# cardspoofer.net
KiCad netlist of a schematic drawn in EAGLE
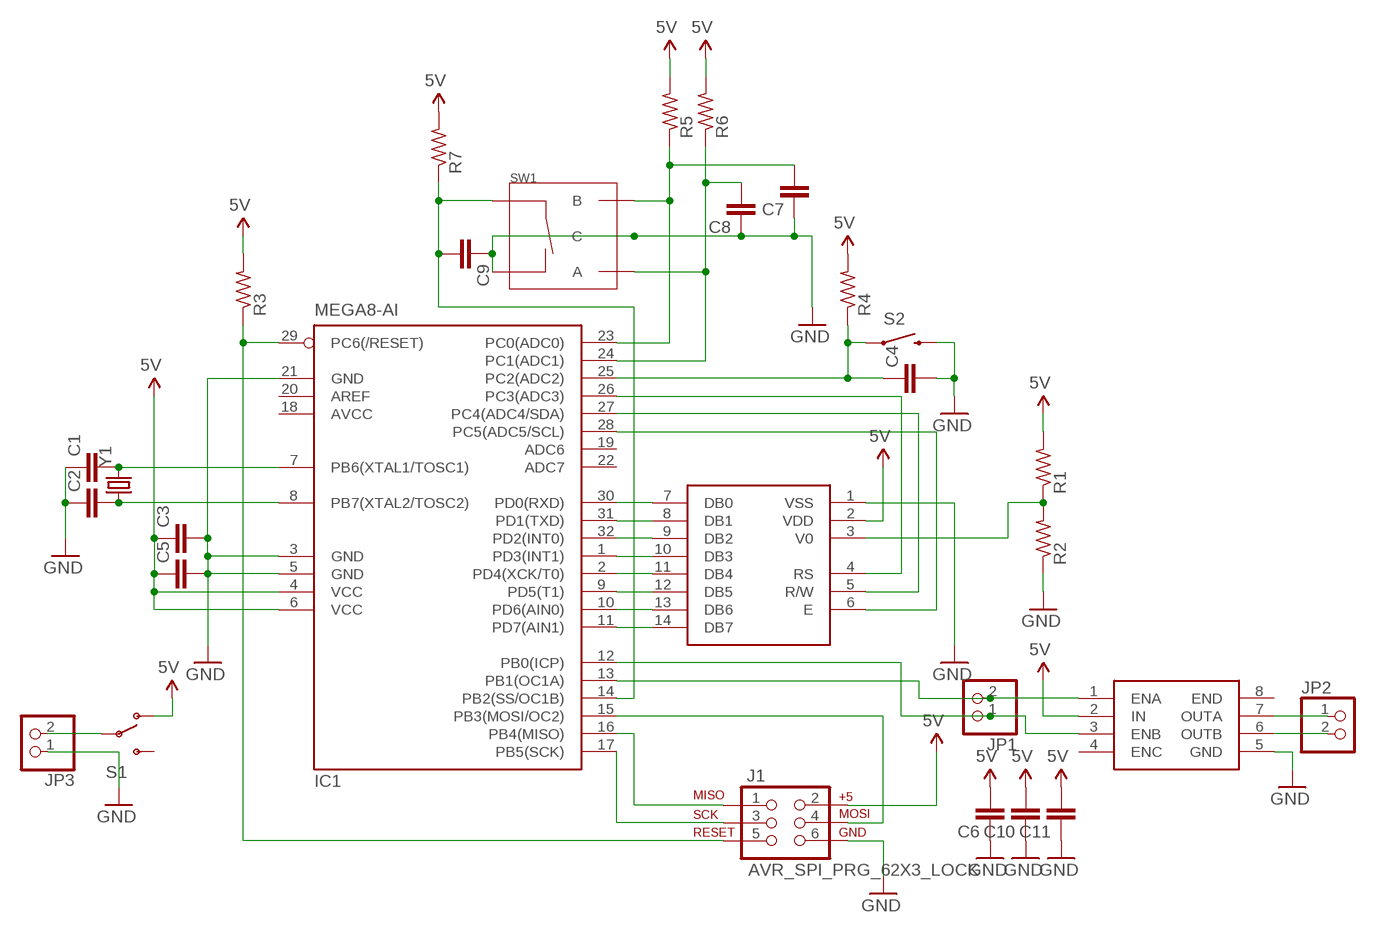
[diagram p0: schematic, sheet 1]

(export (version "E")
  (design (tool "Eeschema 10.0.6"))
  (components
    (comp (ref "C1")
      (value "C-EUC0805K")
      (footprint "eagle-import:C0805K")
      (libsource (lib "eagle-import") (part "C-EUC0805K"))
    )
    (comp (ref "C2")
      (value "C-EUC0805K")
      (footprint "eagle-import:C0805K")
      (libsource (lib "eagle-import") (part "C-EUC0805K"))
    )
    (comp (ref "C3")
      (value "C-EUC0805K")
      (footprint "eagle-import:C0805K")
      (libsource (lib "eagle-import") (part "C-EUC0805K"))
    )
    (comp (ref "C4")
      (value "C-EUC0805K")
      (footprint "eagle-import:C0805K")
      (libsource (lib "eagle-import") (part "C-EUC0805K"))
    )
    (comp (ref "C5")
      (value "C-EUC0805K")
      (footprint "eagle-import:C0805K")
      (libsource (lib "eagle-import") (part "C-EUC0805K"))
    )
    (comp (ref "C6")
      (value "C-EUC0805K")
      (footprint "eagle-import:C0805K")
      (libsource (lib "eagle-import") (part "C-EUC0805K"))
    )
    (comp (ref "C7")
      (value "C-EUC0805K")
      (footprint "eagle-import:C0805K")
      (libsource (lib "eagle-import") (part "C-EUC0805K"))
    )
    (comp (ref "C8")
      (value "C-EUC0805K")
      (footprint "eagle-import:C0805K")
      (libsource (lib "eagle-import") (part "C-EUC0805K"))
    )
    (comp (ref "C9")
      (value "C-EUC0805K")
      (footprint "eagle-import:C0805K")
      (libsource (lib "eagle-import") (part "C-EUC0805K"))
    )
    (comp (ref "C10")
      (value "C-EUC0805K")
      (footprint "eagle-import:C0805K")
      (libsource (lib "eagle-import") (part "C-EUC0805K"))
    )
    (comp (ref "C11")
      (value "C-EUC0805K")
      (footprint "eagle-import:C0805K")
      (libsource (lib "eagle-import") (part "C-EUC0805K"))
    )
    (comp (ref "IC1")
      (value "MEGA8-AI")
      (footprint "eagle-import:TQFP32-08")
      (fields (field (name "MPN") "ATMEGA8-16AU"))
      (libsource (lib "eagle-import") (part "MEGA8-AI"))
    )
    (comp (ref "J1")
      (value "AVR_SPI_PRG_62X3_LOCK")
      (footprint "eagle-import:2X3_LOCK")
      (libsource (lib "eagle-import") (part "AVR_SPI_PRG_62X3_LOCK"))
    )
    (comp (ref "JP1")
      (value "PINHD-1X2")
      (footprint "eagle-import:1X02")
      (libsource (lib "eagle-import") (part "PINHD-1X2"))
    )
    (comp (ref "JP2")
      (value "PINHD-1X2")
      (footprint "eagle-import:1X02")
      (libsource (lib "eagle-import") (part "PINHD-1X2"))
    )
    (comp (ref "JP3")
      (value "PINHD-1X2")
      (footprint "eagle-import:1X02")
      (libsource (lib "eagle-import") (part "PINHD-1X2"))
    )
    (comp (ref "R1")
      (value "R-US_R0805")
      (footprint "eagle-import:R0805")
      (libsource (lib "eagle-import") (part "R-US_R0805"))
    )
    (comp (ref "R2")
      (value "R-US_R0805")
      (footprint "eagle-import:R0805")
      (libsource (lib "eagle-import") (part "R-US_R0805"))
    )
    (comp (ref "R3")
      (value "R-US_R0805")
      (footprint "eagle-import:R0805")
      (libsource (lib "eagle-import") (part "R-US_R0805"))
    )
    (comp (ref "R4")
      (value "R-US_R0805")
      (footprint "eagle-import:R0805")
      (libsource (lib "eagle-import") (part "R-US_R0805"))
    )
    (comp (ref "R5")
      (value "R-US_R0805")
      (footprint "eagle-import:R0805")
      (libsource (lib "eagle-import") (part "R-US_R0805"))
    )
    (comp (ref "R6")
      (value "R-US_R0805")
      (footprint "eagle-import:R0805")
      (libsource (lib "eagle-import") (part "R-US_R0805"))
    )
    (comp (ref "R7")
      (value "R-US_R0805")
      (footprint "eagle-import:R0805")
      (libsource (lib "eagle-import") (part "R-US_R0805"))
    )
    (comp (ref "S1")
      (value "SWITCH-SPDTSMD")
      (footprint "eagle-import:AYZ0202")
      (libsource (lib "eagle-import") (part "SWITCH-SPDTSMD"))
    )
    (comp (ref "S2")
      (value "SWITCH-MOMENTARY-2-SMD-1101NE")
      (footprint "eagle-import:TACTILE-SWITCH-1101NE")
      (libsource (lib "eagle-import") (part "SWITCH-MOMENTARY-2-SMD-1101NE"))
    )
    (comp (ref "SW1")
      (value "ROTARTY_ENCODER")
      (footprint "eagle-import:ROTARY_ENC_PLAIN")
      (libsource (lib "eagle-import") (part "ROTARTY_ENCODER"))
    )
    (comp (ref "U$1")
      (value "LCD")
      (footprint "eagle-import:NHD-0208AZ-RN-YBW-ND")
      (libsource (lib "eagle-import") (part "LCD"))
    )
    (comp (ref "U$2")
      (value "HBRIDGE")
      (footprint "eagle-import:H-BRIDGE")
      (libsource (lib "eagle-import") (part "HBRIDGE"))
    )
    (comp (ref "Y1")
      (value "CRYSTAL5X3")
      (footprint "eagle-import:CRYSTAL-SMD-5X3")
      (libsource (lib "eagle-import") (part "CRYSTAL5X3"))
    )
  )
  (nets
    (net (code "1") (name "/AVCC") (class "Default")
      (node (ref "IC1") (pin "18") (pinfunction "AVCC_18") (pintype "power_in"))
    )
    (net (code "2") (name "5V") (class "Default")
      (node (ref "C10") (pin "2") (pinfunction "2_2") (pintype "passive"))
      (node (ref "C11") (pin "2") (pinfunction "2_2") (pintype "passive"))
      (node (ref "C3") (pin "1") (pinfunction "1_1") (pintype "passive"))
      (node (ref "C5") (pin "1") (pinfunction "1_1") (pintype "passive"))
      (node (ref "C6") (pin "2") (pinfunction "2_2") (pintype "passive"))
      (node (ref "IC1") (pin "4") (pinfunction "VCC_4") (pintype "power_in"))
      (node (ref "IC1") (pin "6") (pinfunction "VCC_6") (pintype "power_in"))
      (node (ref "J1") (pin "2") (pinfunction "2_2") (pintype "passive"))
      (node (ref "R1") (pin "2") (pinfunction "2_2") (pintype "passive"))
      (node (ref "R3") (pin "2") (pinfunction "2_2") (pintype "passive"))
      (node (ref "R4") (pin "2") (pinfunction "2_2") (pintype "passive"))
      (node (ref "R5") (pin "2") (pinfunction "2_2") (pintype "passive"))
      (node (ref "R6") (pin "2") (pinfunction "2_2") (pintype "passive"))
      (node (ref "R7") (pin "2") (pinfunction "2_2") (pintype "passive"))
      (node (ref "S1") (pin "1") (pinfunction "O_1") (pintype "passive"))
      (node (ref "U$1") (pin "2") (pinfunction "VDD_2") (pintype "bidirectional"))
      (node (ref "U$2") (pin "2") (pinfunction "IN_2") (pintype "bidirectional"))
    )
    (net (code "3") (name "GND") (class "Default")
      (node (ref "C1") (pin "1") (pinfunction "1_1") (pintype "passive"))
      (node (ref "C10") (pin "1") (pinfunction "1_1") (pintype "passive"))
      (node (ref "C11") (pin "1") (pinfunction "1_1") (pintype "passive"))
      (node (ref "C2") (pin "1") (pinfunction "1_1") (pintype "passive"))
      (node (ref "C3") (pin "2") (pinfunction "2_2") (pintype "passive"))
      (node (ref "C4") (pin "2") (pinfunction "2_2") (pintype "passive"))
      (node (ref "C5") (pin "2") (pinfunction "2_2") (pintype "passive"))
      (node (ref "C6") (pin "1") (pinfunction "1_1") (pintype "passive"))
      (node (ref "C7") (pin "1") (pinfunction "1_1") (pintype "passive"))
      (node (ref "C8") (pin "1") (pinfunction "1_1") (pintype "passive"))
      (node (ref "C9") (pin "1") (pinfunction "1_1") (pintype "passive"))
      (node (ref "IC1") (pin "21") (pinfunction "GND_21") (pintype "power_in"))
      (node (ref "IC1") (pin "3") (pinfunction "GND_3") (pintype "power_in"))
      (node (ref "IC1") (pin "5") (pinfunction "GND_5") (pintype "power_in"))
      (node (ref "J1") (pin "6") (pinfunction "6_6") (pintype "passive"))
      (node (ref "JP3") (pin "1") (pinfunction "1_1") (pintype "passive"))
      (node (ref "R2") (pin "1") (pinfunction "1_1") (pintype "passive"))
      (node (ref "S2") (pin "2") (pinfunction "2_2") (pintype "passive"))
      (node (ref "SW1") (pin "C") (pinfunction "C_C") (pintype "bidirectional"))
      (node (ref "SW1") (pin "SW-") (pinfunction "SW-_SW-") (pintype "bidirectional"))
      (node (ref "U$1") (pin "1") (pinfunction "VSS_1") (pintype "bidirectional"))
      (node (ref "U$2") (pin "5") (pinfunction "GND_5") (pintype "bidirectional"))
    )
    (net (code "4") (name "Net-(IC1-PB0(ICP))") (class "Default")
      (node (ref "IC1") (pin "12") (pinfunction "PB0(ICP)_12") (pintype "bidirectional"))
      (node (ref "JP1") (pin "1") (pinfunction "1_1") (pintype "passive"))
      (node (ref "U$2") (pin "3") (pinfunction "ENB_3") (pintype "bidirectional"))
    )
    (net (code "5") (name "Net-(IC1-PB1(OC1A))") (class "Default")
      (node (ref "IC1") (pin "13") (pinfunction "PB1(OC1A)_13") (pintype "bidirectional"))
      (node (ref "JP1") (pin "2") (pinfunction "2_2") (pintype "passive"))
      (node (ref "U$2") (pin "1") (pinfunction "ENA_1") (pintype "bidirectional"))
    )
    (net (code "6") (name "Net-(IC1-PB2(SS{slash}OC1B))") (class "Default")
      (node (ref "C9") (pin "2") (pinfunction "2_2") (pintype "passive"))
      (node (ref "IC1") (pin "14") (pinfunction "PB2(SS/OC1B)_14") (pintype "bidirectional"))
      (node (ref "R7") (pin "1") (pinfunction "1_1") (pintype "passive"))
      (node (ref "SW1") (pin "SW+") (pinfunction "SW+_SW+") (pintype "bidirectional"))
    )
    (net (code "7") (name "Net-(IC1-PB3(MOSI{slash}OC2))") (class "Default")
      (node (ref "IC1") (pin "15") (pinfunction "PB3(MOSI/OC2)_15") (pintype "bidirectional"))
      (node (ref "J1") (pin "4") (pinfunction "4_4") (pintype "passive"))
    )
    (net (code "8") (name "Net-(IC1-PB4(MISO))") (class "Default")
      (node (ref "IC1") (pin "16") (pinfunction "PB4(MISO)_16") (pintype "bidirectional"))
      (node (ref "J1") (pin "1") (pinfunction "1_1") (pintype "passive"))
    )
    (net (code "9") (name "Net-(IC1-PB5(SCK))") (class "Default")
      (node (ref "IC1") (pin "17") (pinfunction "PB5(SCK)_17") (pintype "bidirectional"))
      (node (ref "J1") (pin "3") (pinfunction "3_3") (pintype "passive"))
    )
    (net (code "10") (name "Net-(IC1-PB6(XTAL1{slash}TOSC1))") (class "Default")
      (node (ref "C1") (pin "2") (pinfunction "2_2") (pintype "passive"))
      (node (ref "IC1") (pin "7") (pinfunction "PB6(XTAL1/TOSC1)_7") (pintype "bidirectional"))
      (node (ref "Y1") (pin "3") (pinfunction "2_3") (pintype "passive"))
    )
    (net (code "11") (name "Net-(IC1-PB7(XTAL2{slash}TOSC2))") (class "Default")
      (node (ref "C2") (pin "2") (pinfunction "2_2") (pintype "passive"))
      (node (ref "IC1") (pin "8") (pinfunction "PB7(XTAL2/TOSC2)_8") (pintype "bidirectional"))
      (node (ref "Y1") (pin "1") (pinfunction "1_1") (pintype "passive"))
    )
    (net (code "12") (name "Net-(IC1-PC0(ADC0))") (class "Default")
      (node (ref "C7") (pin "2") (pinfunction "2_2") (pintype "passive"))
      (node (ref "IC1") (pin "23") (pinfunction "PC0(ADC0)_23") (pintype "bidirectional"))
      (node (ref "R5") (pin "1") (pinfunction "1_1") (pintype "passive"))
      (node (ref "SW1") (pin "B") (pinfunction "B_B") (pintype "bidirectional"))
    )
    (net (code "13") (name "Net-(IC1-PC1(ADC1))") (class "Default")
      (node (ref "C8") (pin "2") (pinfunction "2_2") (pintype "passive"))
      (node (ref "IC1") (pin "24") (pinfunction "PC1(ADC1)_24") (pintype "bidirectional"))
      (node (ref "R6") (pin "1") (pinfunction "1_1") (pintype "passive"))
      (node (ref "SW1") (pin "A") (pinfunction "A_A") (pintype "bidirectional"))
    )
    (net (code "14") (name "Net-(IC1-PC2(ADC2))") (class "Default")
      (node (ref "C4") (pin "1") (pinfunction "1_1") (pintype "passive"))
      (node (ref "IC1") (pin "25") (pinfunction "PC2(ADC2)_25") (pintype "bidirectional"))
      (node (ref "R4") (pin "1") (pinfunction "1_1") (pintype "passive"))
      (node (ref "S2") (pin "1") (pinfunction "1_1") (pintype "passive"))
    )
    (net (code "15") (name "Net-(IC1-PC3(ADC3))") (class "Default")
      (node (ref "IC1") (pin "26") (pinfunction "PC3(ADC3)_26") (pintype "bidirectional"))
      (node (ref "U$1") (pin "4") (pinfunction "RS_4") (pintype "bidirectional"))
    )
    (net (code "16") (name "Net-(IC1-PC4(ADC4{slash}SDA))") (class "Default")
      (node (ref "IC1") (pin "27") (pinfunction "PC4(ADC4/SDA)_27") (pintype "bidirectional"))
      (node (ref "U$1") (pin "5") (pinfunction "R/W_5") (pintype "bidirectional"))
    )
    (net (code "17") (name "Net-(IC1-PC5(ADC5{slash}SCL))") (class "Default")
      (node (ref "IC1") (pin "28") (pinfunction "PC5(ADC5/SCL)_28") (pintype "bidirectional"))
      (node (ref "U$1") (pin "6") (pinfunction "E_6") (pintype "bidirectional"))
    )
    (net (code "18") (name "Net-(IC1-PC6({slash}RESET))") (class "Default")
      (node (ref "IC1") (pin "29") (pinfunction "PC6(/RESET)_29") (pintype "bidirectional"))
      (node (ref "J1") (pin "5") (pinfunction "5_5") (pintype "passive"))
      (node (ref "R3") (pin "1") (pinfunction "1_1") (pintype "passive"))
    )
    (net (code "19") (name "Net-(IC1-PD0(RXD))") (class "Default")
      (node (ref "IC1") (pin "30") (pinfunction "PD0(RXD)_30") (pintype "bidirectional"))
      (node (ref "U$1") (pin "7") (pinfunction "DB0_7") (pintype "bidirectional"))
    )
    (net (code "20") (name "Net-(IC1-PD1(TXD))") (class "Default")
      (node (ref "IC1") (pin "31") (pinfunction "PD1(TXD)_31") (pintype "bidirectional"))
      (node (ref "U$1") (pin "8") (pinfunction "DB1_8") (pintype "bidirectional"))
    )
    (net (code "21") (name "Net-(IC1-PD2(INT0))") (class "Default")
      (node (ref "IC1") (pin "32") (pinfunction "PD2(INT0)_32") (pintype "bidirectional"))
      (node (ref "U$1") (pin "9") (pinfunction "DB2_9") (pintype "bidirectional"))
    )
    (net (code "22") (name "Net-(IC1-PD3(INT1))") (class "Default")
      (node (ref "IC1") (pin "1") (pinfunction "PD3(INT1)_1") (pintype "bidirectional"))
      (node (ref "U$1") (pin "10") (pinfunction "DB3_10") (pintype "bidirectional"))
    )
    (net (code "23") (name "Net-(IC1-PD4(XCK{slash}T0))") (class "Default")
      (node (ref "IC1") (pin "2") (pinfunction "PD4(XCK/T0)_2") (pintype "bidirectional"))
      (node (ref "U$1") (pin "11") (pinfunction "DB4_11") (pintype "bidirectional"))
    )
    (net (code "24") (name "Net-(IC1-PD5(T1))") (class "Default")
      (node (ref "IC1") (pin "9") (pinfunction "PD5(T1)_9") (pintype "bidirectional"))
      (node (ref "U$1") (pin "12") (pinfunction "DB5_12") (pintype "bidirectional"))
    )
    (net (code "25") (name "Net-(IC1-PD6(AIN0))") (class "Default")
      (node (ref "IC1") (pin "10") (pinfunction "PD6(AIN0)_10") (pintype "bidirectional"))
      (node (ref "U$1") (pin "13") (pinfunction "DB6_13") (pintype "bidirectional"))
    )
    (net (code "26") (name "Net-(IC1-PD7(AIN1))") (class "Default")
      (node (ref "IC1") (pin "11") (pinfunction "PD7(AIN1)_11") (pintype "bidirectional"))
      (node (ref "U$1") (pin "14") (pinfunction "DB7_14") (pintype "bidirectional"))
    )
    (net (code "27") (name "Net-(S1-P)") (class "Default")
      (node (ref "JP3") (pin "2") (pinfunction "2_2") (pintype "passive"))
      (node (ref "S1") (pin "2") (pinfunction "P_2") (pintype "passive"))
    )
    (net (code "28") (name "Net-(U$1-V0)") (class "Default")
      (node (ref "R1") (pin "1") (pinfunction "1_1") (pintype "passive"))
      (node (ref "R2") (pin "2") (pinfunction "2_2") (pintype "passive"))
      (node (ref "U$1") (pin "3") (pinfunction "V0_3") (pintype "bidirectional"))
    )
    (net (code "29") (name "Net-(U$2-OUTA)") (class "Default")
      (node (ref "JP2") (pin "1") (pinfunction "1_1") (pintype "passive"))
      (node (ref "U$2") (pin "7") (pinfunction "OUTA_7") (pintype "bidirectional"))
    )
    (net (code "30") (name "Net-(U$2-OUTB)") (class "Default")
      (node (ref "JP2") (pin "2") (pinfunction "2_2") (pintype "passive"))
      (node (ref "U$2") (pin "6") (pinfunction "OUTB_6") (pintype "bidirectional"))
    )
    (net (code "31") (name "unconnected-(IC1-ADC6-Pad19)") (class "Default")
      (node (ref "IC1") (pin "19") (pinfunction "ADC6_19") (pintype "bidirectional"))
    )
    (net (code "32") (name "unconnected-(IC1-ADC7-Pad22)") (class "Default")
      (node (ref "IC1") (pin "22") (pinfunction "ADC7_22") (pintype "bidirectional"))
    )
    (net (code "33") (name "unconnected-(IC1-AREF-Pad20)") (class "Default")
      (node (ref "IC1") (pin "20") (pinfunction "AREF_20") (pintype "passive"))
    )
    (net (code "34") (name "unconnected-(S1-S-Pad3)") (class "Default")
      (node (ref "S1") (pin "3") (pinfunction "S_3") (pintype "passive"))
    )
    (net (code "35") (name "unconnected-(U$2-ENC-Pad4)") (class "Default")
      (node (ref "U$2") (pin "4") (pinfunction "ENC_4") (pintype "bidirectional"))
    )
    (net (code "36") (name "unconnected-(U$2-END-Pad8)") (class "Default")
      (node (ref "U$2") (pin "8") (pinfunction "END_8") (pintype "bidirectional"))
    )
  )
)
